# Misc.net
KiCad netlist of a schematic drawn in Altium Designer
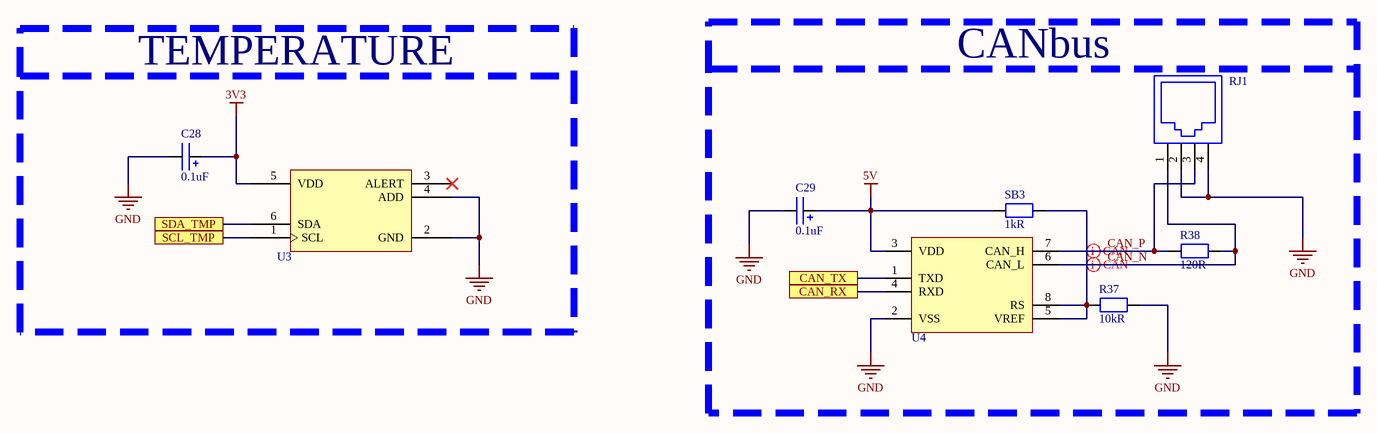
[diagram p0: Misc.SchDoc]

(export (version "E")
  (design (tool "Eeschema 10.0.6"))
  (components
    (comp (ref "C28")
      (value "0.1uF")
      (footprint "CAP 0603")
      (description "Multilayer Ceramic Capacitor")
      (fields (field (name "Comment") "CAP 0603"))
      (libsource (lib "Kaptanyums Lib") (part "CAP 0603"))
    )
    (comp (ref "C29")
      (value "0.1uF")
      (footprint "CAP 0603")
      (description "Multilayer Ceramic Capacitor")
      (fields (field (name "Comment") "CAP 0603"))
      (libsource (lib "Kaptanyums Lib") (part "CAP 0603"))
    )
    (comp (ref "R37")
      (value "10kR")
      (footprint "RESISTOR 0603")
      (description "SMD Chip Resistor")
      (fields (field (name "Comment") "RES 0603"))
      (libsource (lib "Kaptanyums Lib") (part "RES 0603"))
    )
    (comp (ref "R38")
      (value "120R")
      (footprint "RESISTOR 0603")
      (description "SMD Chip Resistor")
      (fields (field (name "Comment") "RES 0603"))
      (libsource (lib "Kaptanyums Lib") (part "RES 0603"))
    )
    (comp (ref "RJ1")
      (value "DS1133-03-S60BX")
      (footprint "RJ6P4C")
      (description "RJ11 Jack")
      (libsource (lib "Kaptanyums Lib") (part "RJ11"))
    )
    (comp (ref "SB3")
      (value "1kR")
      (footprint "RESISTOR 0603")
      (description "SMD Chip Resistor")
      (fields (field (name "Comment") "RES 0603"))
      (libsource (lib "Kaptanyums Lib") (part "RES 0603"))
    )
    (comp (ref "U3")
      (value "TMP112AIDRLT")
      (footprint "SOT563")
      (description "Temp Sensor")
      (libsource (lib "Kaptanyums Lib") (part "TMP112AIDRLT"))
    )
    (comp (ref "U4")
      (value "MCP2551T-I")
      (footprint "SOIC-8")
      (description "CAN Transceiver")
      (libsource (lib "Kaptanyums Lib") (part "MCP2551T-I"))
    )
  )
  (nets
    (net (code "1") (name "/CAN_N") (class "Default")
      (node (ref "R38") (pin "2") (pinfunction "2_2") (pintype "passive"))
      (node (ref "RJ1") (pin "1") (pinfunction "1_1") (pintype "passive"))
      (node (ref "U4") (pin "6") (pinfunction "CAN_L_6") (pintype "passive"))
    )
    (net (code "2") (name "/CAN_P") (class "Default")
      (node (ref "R38") (pin "1") (pinfunction "1_1") (pintype "passive"))
      (node (ref "RJ1") (pin "3") (pinfunction "3_3") (pintype "passive"))
      (node (ref "U4") (pin "7") (pinfunction "CAN_H_7") (pintype "passive"))
    )
    (net (code "3") (name "/CAN_RX") (class "Default")
      (node (ref "U4") (pin "4") (pinfunction "RXD_4") (pintype "passive"))
    )
    (net (code "4") (name "/CAN_TX") (class "Default")
      (node (ref "U4") (pin "1") (pinfunction "TXD_1") (pintype "passive"))
    )
    (net (code "5") (name "/SCL_TMP") (class "Default")
      (node (ref "U3") (pin "1") (pinfunction "SCL_1") (pintype "passive"))
    )
    (net (code "6") (name "/SDA_TMP") (class "Default")
      (node (ref "U3") (pin "6") (pinfunction "SDA_6") (pintype "passive"))
    )
    (net (code "7") (name "3V3") (class "Default")
      (node (ref "C28") (pin "1") (pinfunction "1_1") (pintype "passive"))
      (node (ref "U3") (pin "5") (pinfunction "VDD_5") (pintype "passive"))
    )
    (net (code "8") (name "5V") (class "Default")
      (node (ref "C29") (pin "1") (pinfunction "1_1") (pintype "passive"))
      (node (ref "SB3") (pin "2") (pinfunction "2_2") (pintype "passive"))
      (node (ref "U4") (pin "3") (pinfunction "VDD_3") (pintype "passive"))
    )
    (net (code "9") (name "GND") (class "Default")
      (node (ref "C28") (pin "2") (pinfunction "2_2") (pintype "passive"))
      (node (ref "C29") (pin "2") (pinfunction "2_2") (pintype "passive"))
      (node (ref "R37") (pin "1") (pinfunction "1_1") (pintype "passive"))
      (node (ref "RJ1") (pin "2") (pinfunction "2_2") (pintype "passive"))
      (node (ref "RJ1") (pin "4") (pinfunction "4_4") (pintype "passive"))
      (node (ref "U3") (pin "2") (pinfunction "GND_2") (pintype "passive"))
      (node (ref "U3") (pin "4") (pinfunction "ADD_4") (pintype "passive"))
      (node (ref "U4") (pin "2") (pinfunction "VSS_2") (pintype "passive"))
    )
    (net (code "10") (name "Net-(U4-RS)") (class "Default")
      (node (ref "R37") (pin "2") (pinfunction "2_2") (pintype "passive"))
      (node (ref "SB3") (pin "1") (pinfunction "1_1") (pintype "passive"))
      (node (ref "U4") (pin "5") (pinfunction "VREF_5") (pintype "passive"))
      (node (ref "U4") (pin "8") (pinfunction "RS_8") (pintype "passive"))
    )
    (net (code "11") (name "unconnected-(U3-ALERT-Pad3)") (class "Default")
      (node (ref "U3") (pin "3") (pinfunction "ALERT_3") (pintype "passive+no_connect"))
    )
  )
)
